# Drv8301.net
KiCad netlist of a schematic drawn in Altium Designer
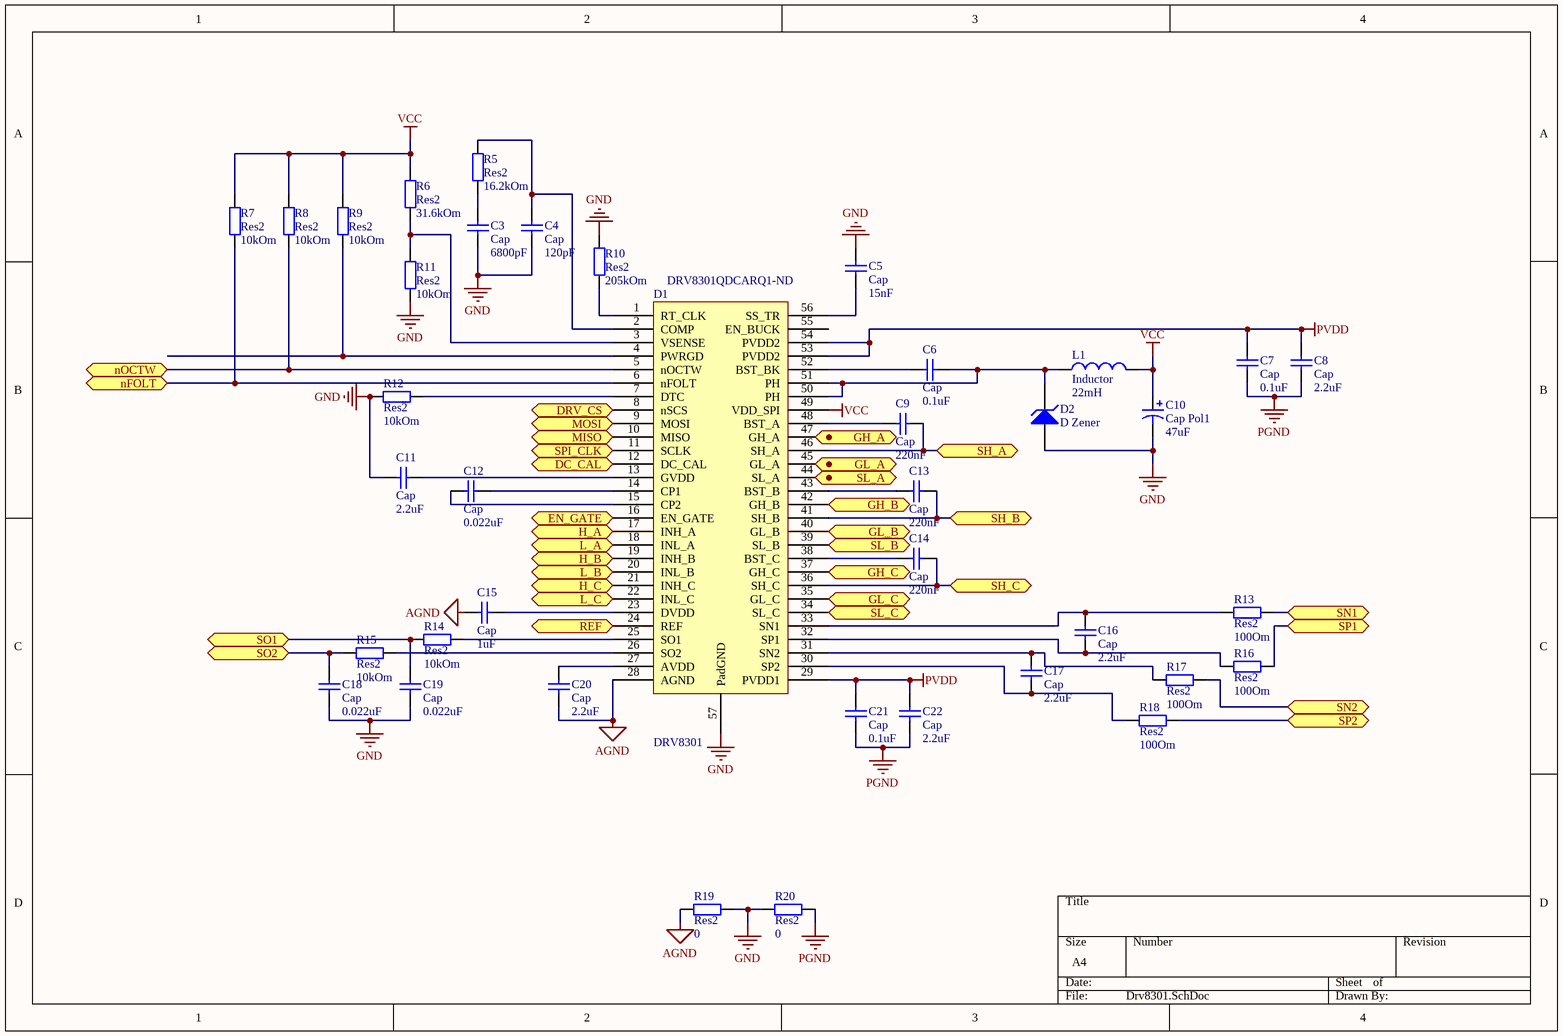
[diagram p0: Drv8301.SchDoc]

(export (version "E")
  (design (tool "Eeschema 10.0.6"))
  (components
    (comp (ref "C3")
      (value "Cap")
      (footprint "6-0805_N")
      (description "Capacitor")
      (fields (field (name "ALTIUM_VALUE") "6800pF") (field (name "PUBLISHER") "Altium Limited"))
      (libsource (lib "Miscellaneous Devices") (part "Cap"))
    )
    (comp (ref "C4")
      (value "Cap")
      (footprint "6-0805_N")
      (description "Capacitor")
      (fields (field (name "ALTIUM_VALUE") "120pF") (field (name "PUBLISHER") "Altium Limited"))
      (libsource (lib "Miscellaneous Devices") (part "Cap"))
    )
    (comp (ref "C5")
      (value "Cap")
      (footprint "6-0805_N")
      (description "Capacitor")
      (fields (field (name "ALTIUM_VALUE") "15nF") (field (name "PUBLISHER") "Altium Limited"))
      (libsource (lib "Miscellaneous Devices") (part "Cap"))
    )
    (comp (ref "C6")
      (value "Cap")
      (footprint "6-0805_N")
      (description "Capacitor")
      (fields (field (name "ALTIUM_VALUE") "0.1uF") (field (name "PUBLISHER") "Altium Limited"))
      (libsource (lib "Miscellaneous Devices") (part "Cap"))
    )
    (comp (ref "C7")
      (value "Cap")
      (footprint "C1206")
      (description "Capacitor")
      (fields (field (name "ALTIUM_VALUE") "0.1uF") (field (name "PUBLISHER") "Altium Limited"))
      (libsource (lib "Miscellaneous Devices") (part "Cap"))
    )
    (comp (ref "C8")
      (value "Cap")
      (footprint "C1206")
      (description "Capacitor")
      (fields (field (name "ALTIUM_VALUE") "2.2uF") (field (name "PUBLISHER") "Altium Limited"))
      (libsource (lib "Miscellaneous Devices") (part "Cap"))
    )
    (comp (ref "C9")
      (value "Cap")
      (footprint "RAD-0.3")
      (description "Capacitor")
      (fields (field (name "ALTIUM_VALUE") "220nF") (field (name "PUBLISHER") "Altium Limited"))
      (libsource (lib "Miscellaneous Devices") (part "Cap"))
    )
    (comp (ref "C10")
      (value "Cap Pol1")
      (footprint "C1210_N")
      (description "Polarized Capacitor (Radial)")
      (fields (field (name "ALTIUM_VALUE") "47uF") (field (name "PUBLISHER") "Altium Limited"))
      (libsource (lib "Miscellaneous Devices") (part "Cap Pol1"))
    )
    (comp (ref "C11")
      (value "Cap")
      (footprint "C1210_N")
      (description "Capacitor")
      (fields (field (name "ALTIUM_VALUE") "2.2uF") (field (name "PUBLISHER") "Altium Limited"))
      (libsource (lib "Miscellaneous Devices") (part "Cap"))
    )
    (comp (ref "C12")
      (value "Cap")
      (footprint "6-0805_N")
      (description "Capacitor")
      (fields (field (name "ALTIUM_VALUE") "0.022uF") (field (name "PUBLISHER") "Altium Limited"))
      (libsource (lib "Miscellaneous Devices") (part "Cap"))
    )
    (comp (ref "C13")
      (value "Cap")
      (footprint "RAD-0.3")
      (description "Capacitor")
      (fields (field (name "ALTIUM_VALUE") "220nF") (field (name "PUBLISHER") "Altium Limited"))
      (libsource (lib "Miscellaneous Devices") (part "Cap"))
    )
    (comp (ref "C14")
      (value "Cap")
      (footprint "RAD-0.3")
      (description "Capacitor")
      (fields (field (name "ALTIUM_VALUE") "220nF") (field (name "PUBLISHER") "Altium Limited"))
      (libsource (lib "Miscellaneous Devices") (part "Cap"))
    )
    (comp (ref "C15")
      (value "Cap")
      (footprint "6-0805_N")
      (description "Capacitor")
      (fields (field (name "ALTIUM_VALUE") "1uF") (field (name "PUBLISHER") "Altium Limited"))
      (libsource (lib "Miscellaneous Devices") (part "Cap"))
    )
    (comp (ref "C16")
      (value "Cap")
      (footprint "6-0805_N")
      (description "Capacitor")
      (fields (field (name "ALTIUM_VALUE") "2.2uF") (field (name "PUBLISHER") "Altium Limited"))
      (libsource (lib "Miscellaneous Devices") (part "Cap"))
    )
    (comp (ref "C17")
      (value "Cap")
      (footprint "6-0805_N")
      (description "Capacitor")
      (fields (field (name "ALTIUM_VALUE") "2.2uF") (field (name "PUBLISHER") "Altium Limited"))
      (libsource (lib "Miscellaneous Devices") (part "Cap"))
    )
    (comp (ref "C18")
      (value "Cap")
      (footprint "6-0805_N")
      (description "Capacitor")
      (fields (field (name "ALTIUM_VALUE") "0.022uF") (field (name "PUBLISHER") "Altium Limited"))
      (libsource (lib "Miscellaneous Devices") (part "Cap"))
    )
    (comp (ref "C19")
      (value "Cap")
      (footprint "6-0805_N")
      (description "Capacitor")
      (fields (field (name "ALTIUM_VALUE") "0.022uF") (field (name "PUBLISHER") "Altium Limited"))
      (libsource (lib "Miscellaneous Devices") (part "Cap"))
    )
    (comp (ref "C20")
      (value "Cap")
      (footprint "6-0805_N")
      (description "Capacitor")
      (fields (field (name "ALTIUM_VALUE") "2.2uF") (field (name "PUBLISHER") "Altium Limited"))
      (libsource (lib "Miscellaneous Devices") (part "Cap"))
    )
    (comp (ref "C21")
      (value "Cap")
      (footprint "C1206")
      (description "Capacitor")
      (fields (field (name "ALTIUM_VALUE") "0.1uF") (field (name "PUBLISHER") "Altium Limited"))
      (libsource (lib "Miscellaneous Devices") (part "Cap"))
    )
    (comp (ref "C22")
      (value "Cap")
      (footprint "C1206")
      (description "ECAP-NOPOLAR-4,7mkf")
      (fields (field (name "ALTIUM_VALUE") "2.2uF") (field (name "PUBLISHER") "Altium Limited"))
      (libsource (lib "Miscellaneous Devices") (part "Cap"))
    )
    (comp (ref "D1")
      (value "DRV8301")
      (footprint "HTSSOP56")
      (description "DRV8301 Three-Phase Gate Driver With Dual Current Shunt Amplifiers  and Buck Regulator")
      (fields (field (name "SUPPLIER PART NUMBER 1") "DRV8301QDCARQ1-ND"))
      (libsource (lib "K0_PK8") (part "DRV8301"))
    )
    (comp (ref "D2")
      (value "D Zener")
      (footprint "SMB")
      (description "Zener Diode")
      (fields (field (name "PUBLISHER") "Altium Limited"))
      (libsource (lib "Miscellaneous Devices") (part "D Zener"))
    )
    (comp (ref "L1")
      (value "Inductor")
      (footprint "INDC4532")
      (fields (field (name "ALTIUM_VALUE") "22mH") (field (name "PUBLISHER") "Altium Limited"))
      (libsource (lib "Miscellaneous Devices") (part "Inductor"))
    )
    (comp (ref "R5")
      (value "Res2")
      (footprint "6-0805_N")
      (description "Resistor")
      (fields (field (name "ALTIUM_VALUE") "16.2kOm") (field (name "PUBLISHER") "Altium Limited"))
      (libsource (lib "Miscellaneous Devices") (part "Res2"))
    )
    (comp (ref "R6")
      (value "Res2")
      (footprint "6-0805_N")
      (description "Resistor")
      (fields (field (name "ALTIUM_VALUE") "31.6kOm") (field (name "PUBLISHER") "Altium Limited"))
      (libsource (lib "Miscellaneous Devices") (part "Res2"))
    )
    (comp (ref "R7")
      (value "Res2")
      (footprint "6-0805_N")
      (description "Resistor")
      (fields (field (name "ALTIUM_VALUE") "10kOm") (field (name "PUBLISHER") "Altium Limited"))
      (libsource (lib "Miscellaneous Devices") (part "Res2"))
    )
    (comp (ref "R8")
      (value "Res2")
      (footprint "6-0805_N")
      (description "Resistor")
      (fields (field (name "ALTIUM_VALUE") "10kOm") (field (name "PUBLISHER") "Altium Limited"))
      (libsource (lib "Miscellaneous Devices") (part "Res2"))
    )
    (comp (ref "R9")
      (value "Res2")
      (footprint "6-0805_N")
      (description "Resistor")
      (fields (field (name "ALTIUM_VALUE") "10kOm") (field (name "PUBLISHER") "Altium Limited"))
      (libsource (lib "Miscellaneous Devices") (part "Res2"))
    )
    (comp (ref "R10")
      (value "Res2")
      (footprint "6-0805_N")
      (description "Resistor")
      (fields (field (name "ALTIUM_VALUE") "205kOm") (field (name "PUBLISHER") "Altium Limited"))
      (libsource (lib "Miscellaneous Devices") (part "Res2"))
    )
    (comp (ref "R11")
      (value "Res2")
      (footprint "6-0805_N")
      (description "Resistor")
      (fields (field (name "ALTIUM_VALUE") "10kOm") (field (name "PUBLISHER") "Altium Limited"))
      (libsource (lib "Miscellaneous Devices") (part "Res2"))
    )
    (comp (ref "R12")
      (value "Res2")
      (footprint "6-0805_N")
      (description "Resistor")
      (fields (field (name "ALTIUM_VALUE") "10kOm") (field (name "PUBLISHER") "Altium Limited"))
      (libsource (lib "") (part "Res2_1"))
    )
    (comp (ref "R13")
      (value "Res2")
      (footprint "6-0805_N")
      (description "Resistor")
      (fields (field (name "ALTIUM_VALUE") "100Om") (field (name "PUBLISHER") "Altium Limited"))
      (libsource (lib "") (part "Res2_1"))
    )
    (comp (ref "R14")
      (value "Res2")
      (footprint "6-0805_N")
      (description "Resistor")
      (fields (field (name "ALTIUM_VALUE") "10kOm") (field (name "PUBLISHER") "Altium Limited"))
      (libsource (lib "") (part "Res2_1"))
    )
    (comp (ref "R15")
      (value "Res2")
      (footprint "6-0805_N")
      (description "Resistor")
      (fields (field (name "ALTIUM_VALUE") "10kOm") (field (name "PUBLISHER") "Altium Limited"))
      (libsource (lib "") (part "Res2_1"))
    )
    (comp (ref "R16")
      (value "Res2")
      (footprint "6-0805_N")
      (description "Resistor")
      (fields (field (name "ALTIUM_VALUE") "100Om") (field (name "PUBLISHER") "Altium Limited"))
      (libsource (lib "") (part "Res2_1"))
    )
    (comp (ref "R17")
      (value "Res2")
      (footprint "6-0805_N")
      (description "Resistor")
      (fields (field (name "ALTIUM_VALUE") "100Om") (field (name "PUBLISHER") "Altium Limited"))
      (libsource (lib "") (part "Res2_1"))
    )
    (comp (ref "R18")
      (value "Res2")
      (footprint "6-0805_N")
      (description "Resistor")
      (fields (field (name "ALTIUM_VALUE") "100Om") (field (name "PUBLISHER") "Altium Limited"))
      (libsource (lib "") (part "Res2_1"))
    )
    (comp (ref "R19")
      (value "Res2")
      (footprint "6-0805_N")
      (description "Resistor")
      (fields (field (name "ALTIUM_VALUE") "0") (field (name "PUBLISHER") "Altium Limited"))
      (libsource (lib "") (part "Res2_2"))
    )
    (comp (ref "R20")
      (value "Res2")
      (footprint "6-0805_N")
      (description "Resistor")
      (fields (field (name "ALTIUM_VALUE") "0") (field (name "PUBLISHER") "Altium Limited"))
      (libsource (lib "") (part "Res2_2"))
    )
  )
  (nets
    (net (code "1") (name "/DC_CAL") (class "Default")
      (node (ref "D1") (pin "12") (pinfunction "DC_CAL_12") (pintype "passive"))
    )
    (net (code "2") (name "/DRV_CS") (class "Default")
      (node (ref "D1") (pin "8") (pinfunction "nSCS_8") (pintype "passive"))
    )
    (net (code "3") (name "/EN_GATE") (class "Default")
      (node (ref "D1") (pin "16") (pinfunction "EN_GATE_16") (pintype "passive"))
    )
    (net (code "5") (name "/GH_B") (class "Default")
      (node (ref "D1") (pin "42") (pinfunction "GH_B_42") (pintype "passive"))
    )
    (net (code "6") (name "/GH_C") (class "Default")
      (node (ref "D1") (pin "37") (pinfunction "GH_C_37") (pintype "passive"))
    )
    (net (code "8") (name "/GL_B") (class "Default")
      (node (ref "D1") (pin "40") (pinfunction "GL_B_40") (pintype "passive"))
    )
    (net (code "9") (name "/GL_C") (class "Default")
      (node (ref "D1") (pin "35") (pinfunction "GL_C_35") (pintype "passive"))
    )
    (net (code "10") (name "/H_A") (class "Default")
      (node (ref "D1") (pin "17") (pinfunction "INH_A_17") (pintype "passive"))
    )
    (net (code "11") (name "/H_B") (class "Default")
      (node (ref "D1") (pin "19") (pinfunction "INH_B_19") (pintype "passive"))
    )
    (net (code "12") (name "/H_C") (class "Default")
      (node (ref "D1") (pin "21") (pinfunction "INH_C_21") (pintype "passive"))
    )
    (net (code "13") (name "/L_A") (class "Default")
      (node (ref "D1") (pin "18") (pinfunction "INL_A_18") (pintype "passive"))
    )
    (net (code "14") (name "/L_B") (class "Default")
      (node (ref "D1") (pin "20") (pinfunction "INL_B_20") (pintype "passive"))
    )
    (net (code "15") (name "/L_C") (class "Default")
      (node (ref "D1") (pin "22") (pinfunction "INL_C_22") (pintype "passive"))
    )
    (net (code "16") (name "/MISO") (class "Default")
      (node (ref "D1") (pin "10") (pinfunction "MISO_10") (pintype "passive"))
    )
    (net (code "17") (name "/MOSI") (class "Default")
      (node (ref "D1") (pin "9") (pinfunction "MOSI_9") (pintype "passive"))
    )
    (net (code "18") (name "/REF") (class "Default")
      (node (ref "D1") (pin "24") (pinfunction "REF_24") (pintype "passive"))
    )
    (net (code "19") (name "/SH_A") (class "Default")
      (node (ref "C9") (pin "1") (pinfunction "1_1") (pintype "passive"))
      (node (ref "D1") (pin "46") (pinfunction "SH_A_46") (pintype "passive"))
    )
    (net (code "20") (name "/SH_B") (class "Default")
      (node (ref "C13") (pin "1") (pinfunction "1_1") (pintype "passive"))
      (node (ref "D1") (pin "41") (pinfunction "SH_B_41") (pintype "passive"))
    )
    (net (code "21") (name "/SH_C") (class "Default")
      (node (ref "C14") (pin "1") (pinfunction "1_1") (pintype "passive"))
      (node (ref "D1") (pin "36") (pinfunction "SH_C_36") (pintype "passive"))
    )
    (net (code "23") (name "/SL_B") (class "Default")
      (node (ref "D1") (pin "39") (pinfunction "SL_B_39") (pintype "passive"))
    )
    (net (code "24") (name "/SL_C") (class "Default")
      (node (ref "D1") (pin "34") (pinfunction "SL_C_34") (pintype "passive"))
    )
    (net (code "25") (name "/SN1") (class "Default")
      (node (ref "R13") (pin "1") (pinfunction "1_1") (pintype "passive"))
    )
    (net (code "26") (name "/SN2") (class "Default")
      (node (ref "R17") (pin "1") (pinfunction "1_1") (pintype "passive"))
    )
    (net (code "27") (name "/SO1") (class "Default")
      (node (ref "C19") (pin "2") (pinfunction "2_2") (pintype "passive"))
      (node (ref "R14") (pin "2") (pinfunction "2_2") (pintype "passive"))
    )
    (net (code "28") (name "/SO2") (class "Default")
      (node (ref "C18") (pin "2") (pinfunction "2_2") (pintype "passive"))
      (node (ref "R15") (pin "2") (pinfunction "2_2") (pintype "passive"))
    )
    (net (code "29") (name "/SP1") (class "Default")
      (node (ref "R16") (pin "1") (pinfunction "1_1") (pintype "passive"))
    )
    (net (code "30") (name "/SP2") (class "Default")
      (node (ref "R18") (pin "1") (pinfunction "1_1") (pintype "passive"))
    )
    (net (code "31") (name "/SPI_CLK") (class "Default")
      (node (ref "D1") (pin "11") (pinfunction "SCLK_11") (pintype "passive"))
    )
    (net (code "32") (name "/nFOLT") (class "Default")
      (node (ref "D1") (pin "6") (pinfunction "nFOLT_6") (pintype "passive"))
      (node (ref "R7") (pin "1") (pinfunction "1_1") (pintype "passive"))
    )
    (net (code "33") (name "/nOCTW") (class "Default")
      (node (ref "D1") (pin "5") (pinfunction "nOCTW_5") (pintype "passive"))
      (node (ref "R8") (pin "1") (pinfunction "1_1") (pintype "passive"))
    )
    (net (code "34") (name "AGND") (class "Default")
      (node (ref "C15") (pin "1") (pinfunction "1_1") (pintype "passive"))
      (node (ref "C20") (pin "1") (pinfunction "1_1") (pintype "passive"))
      (node (ref "D1") (pin "28") (pinfunction "AGND_28") (pintype "passive"))
      (node (ref "R19") (pin "1") (pinfunction "1_1") (pintype "passive"))
    )
    (net (code "35") (name "GND") (class "Default")
      (node (ref "C10") (pin "2") (pinfunction "2_2") (pintype "passive"))
      (node (ref "C11") (pin "1") (pinfunction "1_1") (pintype "passive"))
      (node (ref "C18") (pin "1") (pinfunction "1_1") (pintype "passive"))
      (node (ref "C19") (pin "1") (pinfunction "1_1") (pintype "passive"))
      (node (ref "C3") (pin "2") (pinfunction "2_2") (pintype "passive"))
      (node (ref "C4") (pin "2") (pinfunction "2_2") (pintype "passive"))
      (node (ref "C5") (pin "1") (pinfunction "1_1") (pintype "passive"))
      (node (ref "D1") (pin "57") (pinfunction "PadGND_57") (pintype "passive"))
      (node (ref "D2") (pin "1") (pinfunction "A_1") (pintype "passive"))
      (node (ref "R10") (pin "2") (pinfunction "2_2") (pintype "passive"))
      (node (ref "R11") (pin "1") (pinfunction "1_1") (pintype "passive"))
      (node (ref "R12") (pin "2") (pinfunction "2_2") (pintype "passive"))
      (node (ref "R19") (pin "2") (pinfunction "2_2") (pintype "passive"))
      (node (ref "R20") (pin "1") (pinfunction "1_1") (pintype "passive"))
    )
    (net (code "36") (name "Net-(C3-Pad1)") (class "Default")
      (node (ref "C3") (pin "1") (pinfunction "1_1") (pintype "passive"))
      (node (ref "R5") (pin "1") (pinfunction "1_1") (pintype "passive"))
    )
    (net (code "37") (name "Net-(D1-AVDD)") (class "Default")
      (node (ref "C20") (pin "2") (pinfunction "2_2") (pintype "passive"))
      (node (ref "D1") (pin "27") (pinfunction "AVDD_27") (pintype "passive"))
    )
    (net (code "38") (name "Net-(D1-BST_A)") (class "Default")
      (node (ref "C9") (pin "2") (pinfunction "2_2") (pintype "passive"))
      (node (ref "D1") (pin "48") (pinfunction "BST_A_48") (pintype "passive"))
    )
    (net (code "39") (name "Net-(D1-BST_B)") (class "Default")
      (node (ref "C13") (pin "2") (pinfunction "2_2") (pintype "passive"))
      (node (ref "D1") (pin "43") (pinfunction "BST_B_43") (pintype "passive"))
    )
    (net (code "40") (name "Net-(D1-BST_BK)") (class "Default")
      (node (ref "C6") (pin "2") (pinfunction "2_2") (pintype "passive"))
      (node (ref "D1") (pin "52") (pinfunction "BST_BK_52") (pintype "passive"))
    )
    (net (code "41") (name "Net-(D1-BST_C)") (class "Default")
      (node (ref "C14") (pin "2") (pinfunction "2_2") (pintype "passive"))
      (node (ref "D1") (pin "38") (pinfunction "BST_C_38") (pintype "passive"))
    )
    (net (code "42") (name "Net-(D1-COMP)") (class "Default")
      (node (ref "C4") (pin "1") (pinfunction "1_1") (pintype "passive"))
      (node (ref "D1") (pin "2") (pinfunction "COMP_2") (pintype "passive"))
      (node (ref "R5") (pin "2") (pinfunction "2_2") (pintype "passive"))
    )
    (net (code "43") (name "Net-(D1-CP1)") (class "Default")
      (node (ref "C12") (pin "2") (pinfunction "2_2") (pintype "passive"))
      (node (ref "D1") (pin "14") (pinfunction "CP1_14") (pintype "passive"))
    )
    (net (code "44") (name "Net-(D1-CP2)") (class "Default")
      (node (ref "C12") (pin "1") (pinfunction "1_1") (pintype "passive"))
      (node (ref "D1") (pin "15") (pinfunction "CP2_15") (pintype "passive"))
    )
    (net (code "45") (name "Net-(D1-DTC)") (class "Default")
      (node (ref "D1") (pin "7") (pinfunction "DTC_7") (pintype "passive"))
      (node (ref "R12") (pin "1") (pinfunction "1_1") (pintype "passive"))
    )
    (net (code "46") (name "Net-(D1-DVDD)") (class "Default")
      (node (ref "C15") (pin "2") (pinfunction "2_2") (pintype "passive"))
      (node (ref "D1") (pin "23") (pinfunction "DVDD_23") (pintype "passive"))
    )
    (net (code "47") (name "Net-(D1-GVDD)") (class "Default")
      (node (ref "C11") (pin "2") (pinfunction "2_2") (pintype "passive"))
      (node (ref "D1") (pin "13") (pinfunction "GVDD_13") (pintype "passive"))
    )
    (net (code "48") (name "Net-(D1-PWRGD)") (class "Default")
      (node (ref "D1") (pin "4") (pinfunction "PWRGD_4") (pintype "passive"))
      (node (ref "R9") (pin "1") (pinfunction "1_1") (pintype "passive"))
    )
    (net (code "49") (name "Net-(D1-RT_CLK)") (class "Default")
      (node (ref "D1") (pin "1") (pinfunction "RT_CLK_1") (pintype "passive"))
      (node (ref "R10") (pin "1") (pinfunction "1_1") (pintype "passive"))
    )
    (net (code "50") (name "Net-(D1-SN1)") (class "Default")
      (node (ref "C16") (pin "2") (pinfunction "2_2") (pintype "passive"))
      (node (ref "D1") (pin "33") (pinfunction "SN1_33") (pintype "passive"))
      (node (ref "R13") (pin "2") (pinfunction "2_2") (pintype "passive"))
    )
    (net (code "51") (name "Net-(D1-SN2)") (class "Default")
      (node (ref "C17") (pin "2") (pinfunction "2_2") (pintype "passive"))
      (node (ref "D1") (pin "31") (pinfunction "SN2_31") (pintype "passive"))
      (node (ref "R17") (pin "2") (pinfunction "2_2") (pintype "passive"))
    )
    (net (code "52") (name "Net-(D1-SO1)") (class "Default")
      (node (ref "D1") (pin "25") (pinfunction "SO1_25") (pintype "passive"))
      (node (ref "R14") (pin "1") (pinfunction "1_1") (pintype "passive"))
    )
    (net (code "53") (name "Net-(D1-SO2)") (class "Default")
      (node (ref "D1") (pin "26") (pinfunction "SO2_26") (pintype "passive"))
      (node (ref "R15") (pin "1") (pinfunction "1_1") (pintype "passive"))
    )
    (net (code "54") (name "Net-(D1-SP1)") (class "Default")
      (node (ref "C16") (pin "1") (pinfunction "1_1") (pintype "passive"))
      (node (ref "D1") (pin "32") (pinfunction "SP1_32") (pintype "passive"))
      (node (ref "R16") (pin "2") (pinfunction "2_2") (pintype "passive"))
    )
    (net (code "55") (name "Net-(D1-SP2)") (class "Default")
      (node (ref "C17") (pin "1") (pinfunction "1_1") (pintype "passive"))
      (node (ref "D1") (pin "30") (pinfunction "SP2_30") (pintype "passive"))
      (node (ref "R18") (pin "2") (pinfunction "2_2") (pintype "passive"))
    )
    (net (code "56") (name "Net-(D1-SS_TR)") (class "Default")
      (node (ref "C5") (pin "2") (pinfunction "2_2") (pintype "passive"))
      (node (ref "D1") (pin "56") (pinfunction "SS_TR_56") (pintype "passive"))
    )
    (net (code "57") (name "Net-(D1-VSENSE)") (class "Default")
      (node (ref "D1") (pin "3") (pinfunction "VSENSE_3") (pintype "passive"))
      (node (ref "R11") (pin "2") (pinfunction "2_2") (pintype "passive"))
      (node (ref "R6") (pin "1") (pinfunction "1_1") (pintype "passive"))
    )
    (net (code "58") (name "Net-(D2-K)") (class "Default")
      (node (ref "C6") (pin "1") (pinfunction "1_1") (pintype "passive"))
      (node (ref "D1") (pin "50") (pinfunction "PH_50") (pintype "passive"))
      (node (ref "D1") (pin "51") (pinfunction "PH_51") (pintype "passive"))
      (node (ref "D2") (pin "2") (pinfunction "K_2") (pintype "passive"))
      (node (ref "L1") (pin "1") (pinfunction "1_1") (pintype "passive"))
    )
    (net (code "59") (name "PGND") (class "Default")
      (node (ref "C21") (pin "1") (pinfunction "1_1") (pintype "passive"))
      (node (ref "C22") (pin "1") (pinfunction "1_1") (pintype "passive"))
      (node (ref "C7") (pin "1") (pinfunction "1_1") (pintype "passive"))
      (node (ref "C8") (pin "1") (pinfunction "1_1") (pintype "passive"))
      (node (ref "R20") (pin "2") (pinfunction "2_2") (pintype "passive"))
    )
    (net (code "60") (name "PVDD") (class "Default")
      (node (ref "C21") (pin "2") (pinfunction "2_2") (pintype "passive"))
      (node (ref "C22") (pin "2") (pinfunction "2_2") (pintype "passive"))
      (node (ref "C7") (pin "2") (pinfunction "2_2") (pintype "passive"))
      (node (ref "C8") (pin "2") (pinfunction "2_2") (pintype "passive"))
      (node (ref "D1") (pin "29") (pinfunction "PVDD1_29") (pintype "passive"))
      (node (ref "D1") (pin "53") (pinfunction "PVDD2_53") (pintype "passive"))
      (node (ref "D1") (pin "54") (pinfunction "PVDD2_54") (pintype "passive"))
    )
    (net (code "61") (name "VCC") (class "Default")
      (node (ref "C10") (pin "1") (pinfunction "1_1") (pintype "passive"))
      (node (ref "D1") (pin "49") (pinfunction "VDD_SPI_49") (pintype "passive"))
      (node (ref "L1") (pin "2") (pinfunction "2_2") (pintype "passive"))
      (node (ref "R6") (pin "2") (pinfunction "2_2") (pintype "passive"))
      (node (ref "R7") (pin "2") (pinfunction "2_2") (pintype "passive"))
      (node (ref "R8") (pin "2") (pinfunction "2_2") (pintype "passive"))
      (node (ref "R9") (pin "2") (pinfunction "2_2") (pintype "passive"))
    )
    (net (code "62") (name "unconnected-(D1-EN_BUCK-Pad55)") (class "Default")
      (node (ref "D1") (pin "55") (pinfunction "EN_BUCK_55") (pintype "passive"))
    )
    (net (code "63") (name "unconnected-(D1-GH_A-Pad47)") (class "Default")
      (node (ref "D1") (pin "47") (pinfunction "GH_A_47") (pintype "passive"))
    )
    (net (code "64") (name "unconnected-(D1-GL_A-Pad45)") (class "Default")
      (node (ref "D1") (pin "45") (pinfunction "GL_A_45") (pintype "passive"))
    )
    (net (code "65") (name "unconnected-(D1-SL_A-Pad44)") (class "Default")
      (node (ref "D1") (pin "44") (pinfunction "SL_A_44") (pintype "passive"))
    )
  )
)
